# TA_2021_V_2.net
KiCad netlist of a schematic drawn in EAGLE
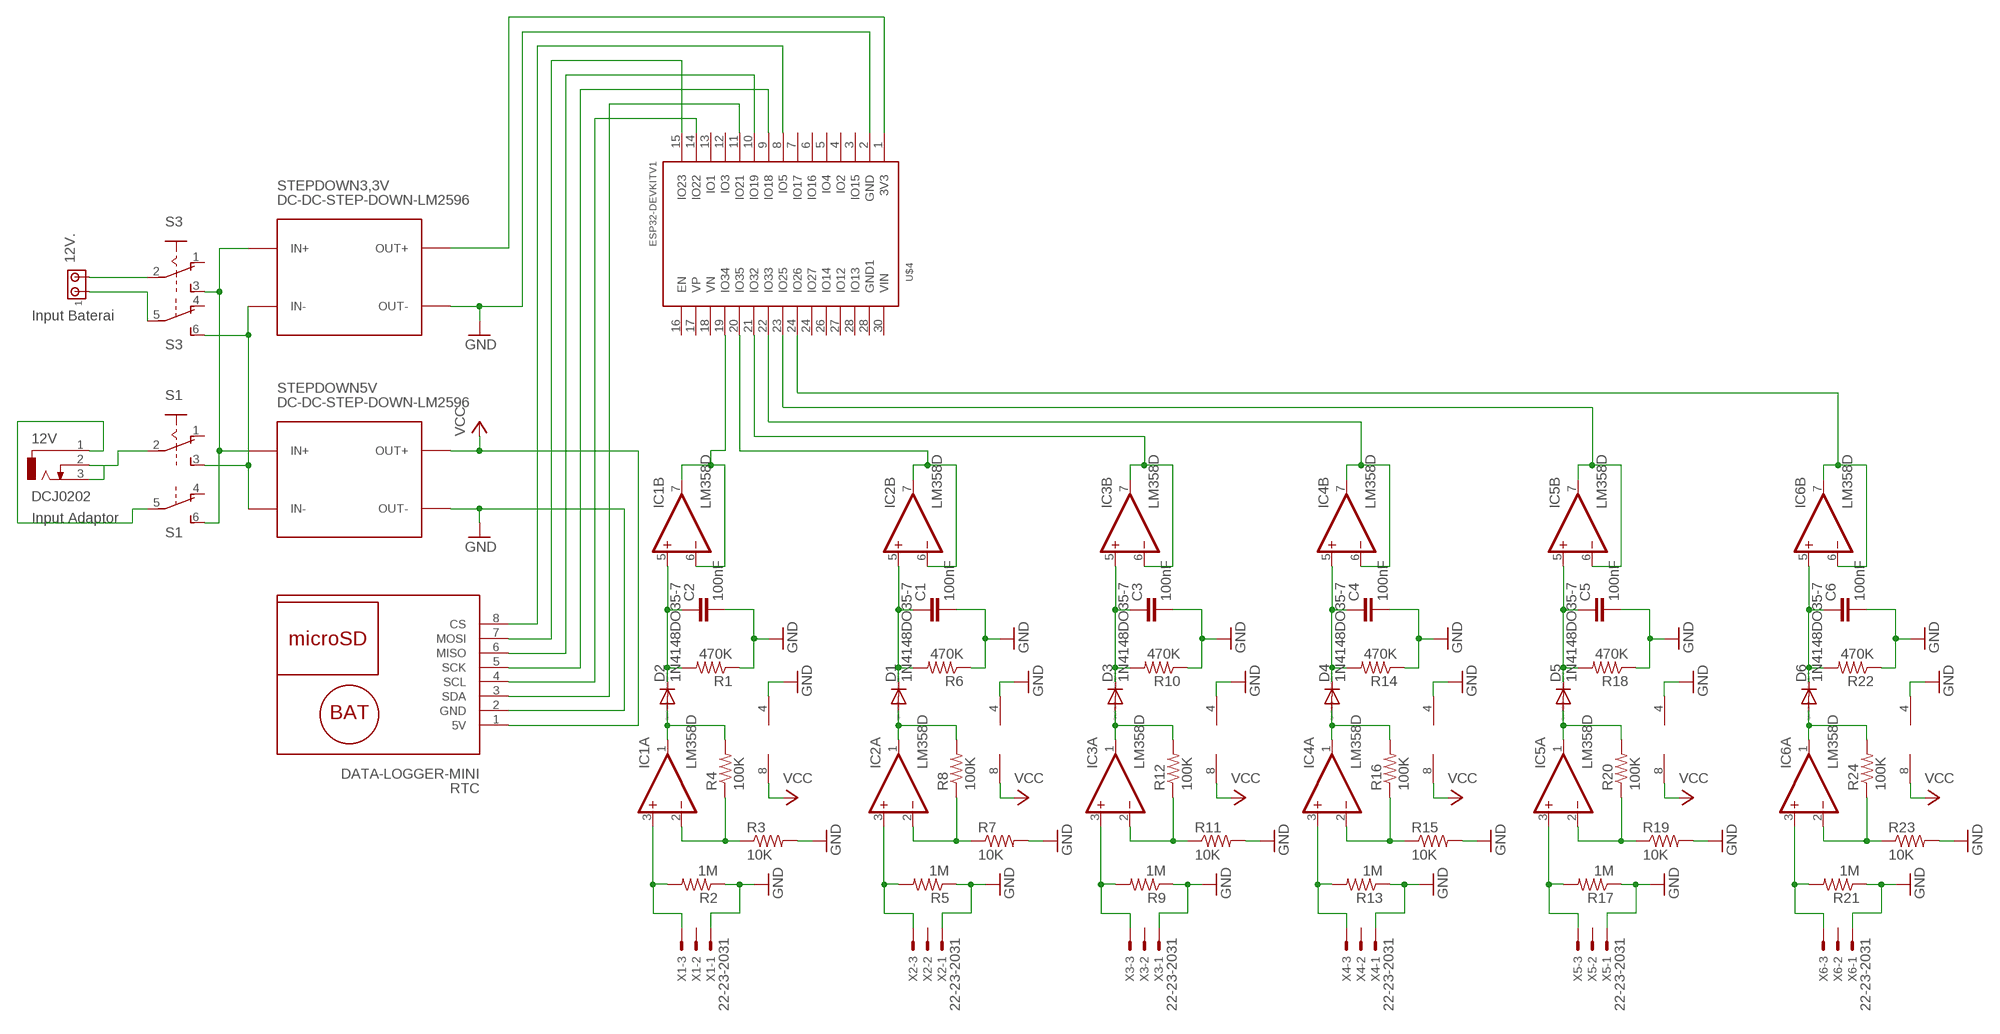
[diagram p0: schematic, sheet 1]

(export (version "E")
  (design (tool "Eeschema 10.0.6"))
  (components
    (comp (ref "12V")
      (value "DCJ0202")
      (footprint "eagle-import:DCJ0202")
      (libsource (lib "eagle-import") (part "DCJ0202"))
    )
    (comp (ref "12V.")
      (value "MTA02-156")
      (footprint "eagle-import:1X2MTA")
      (libsource (lib "eagle-import") (part "MTA02-156"))
    )
    (comp (ref "C1")
      (value "100nF")
      (footprint "eagle-import:C075-032X103")
      (libsource (lib "eagle-import") (part "C-EU075-032X103"))
    )
    (comp (ref "C2")
      (value "100nF")
      (footprint "eagle-import:C075-032X103")
      (libsource (lib "eagle-import") (part "C-EU075-032X103"))
    )
    (comp (ref "C3")
      (value "100nF")
      (footprint "eagle-import:C075-032X103")
      (libsource (lib "eagle-import") (part "C-EU075-032X103"))
    )
    (comp (ref "C4")
      (value "100nF")
      (footprint "eagle-import:C075-032X103")
      (libsource (lib "eagle-import") (part "C-EU075-032X103"))
    )
    (comp (ref "C5")
      (value "100nF")
      (footprint "eagle-import:C075-032X103")
      (libsource (lib "eagle-import") (part "C-EU075-032X103"))
    )
    (comp (ref "C6")
      (value "100nF")
      (footprint "eagle-import:C075-032X103")
      (libsource (lib "eagle-import") (part "C-EU075-032X103"))
    )
    (comp (ref "D1")
      (value "1N4148DO35-7")
      (footprint "eagle-import:DO35-7")
      (libsource (lib "eagle-import") (part "1N4148DO35-7"))
    )
    (comp (ref "D2")
      (value "1N4148DO35-7")
      (footprint "eagle-import:DO35-7")
      (libsource (lib "eagle-import") (part "1N4148DO35-7"))
    )
    (comp (ref "D3")
      (value "1N4148DO35-7")
      (footprint "eagle-import:DO35-7")
      (libsource (lib "eagle-import") (part "1N4148DO35-7"))
    )
    (comp (ref "D4")
      (value "1N4148DO35-7")
      (footprint "eagle-import:DO35-7")
      (libsource (lib "eagle-import") (part "1N4148DO35-7"))
    )
    (comp (ref "D5")
      (value "1N4148DO35-7")
      (footprint "eagle-import:DO35-7")
      (libsource (lib "eagle-import") (part "1N4148DO35-7"))
    )
    (comp (ref "D6")
      (value "1N4148DO35-7")
      (footprint "eagle-import:DO35-7")
      (libsource (lib "eagle-import") (part "1N4148DO35-7"))
    )
    (comp (ref "IC1")
      (value "LM358D")
      (footprint "eagle-import:SO08")
      (libsource (lib "eagle-import") (part "LM358D"))
    )
    (comp (ref "IC2")
      (value "LM358D")
      (footprint "eagle-import:SO08")
      (libsource (lib "eagle-import") (part "LM358D"))
    )
    (comp (ref "IC3")
      (value "LM358D")
      (footprint "eagle-import:SO08")
      (libsource (lib "eagle-import") (part "LM358D"))
    )
    (comp (ref "IC4")
      (value "LM358D")
      (footprint "eagle-import:SO08")
      (libsource (lib "eagle-import") (part "LM358D"))
    )
    (comp (ref "IC5")
      (value "LM358D")
      (footprint "eagle-import:SO08")
      (libsource (lib "eagle-import") (part "LM358D"))
    )
    (comp (ref "IC6")
      (value "LM358D")
      (footprint "eagle-import:SO08")
      (libsource (lib "eagle-import") (part "LM358D"))
    )
    (comp (ref "R1")
      (value "470K")
      (footprint "eagle-import:0207_10")
      (libsource (lib "eagle-import") (part "R-US_0207/10"))
    )
    (comp (ref "R2")
      (value "1M")
      (footprint "eagle-import:0207_10")
      (libsource (lib "eagle-import") (part "R-US_0207/10"))
    )
    (comp (ref "R3")
      (value "10K")
      (footprint "eagle-import:0207_10")
      (libsource (lib "eagle-import") (part "R-US_0207/10"))
    )
    (comp (ref "R4")
      (value "100K")
      (footprint "eagle-import:0207_10")
      (libsource (lib "eagle-import") (part "R-US_0207/10"))
    )
    (comp (ref "R5")
      (value "1M")
      (footprint "eagle-import:0207_10")
      (libsource (lib "eagle-import") (part "R-US_0207/10"))
    )
    (comp (ref "R6")
      (value "470K")
      (footprint "eagle-import:0207_10")
      (libsource (lib "eagle-import") (part "R-US_0207/10"))
    )
    (comp (ref "R7")
      (value "10K")
      (footprint "eagle-import:0207_10")
      (libsource (lib "eagle-import") (part "R-US_0207/10"))
    )
    (comp (ref "R8")
      (value "100K")
      (footprint "eagle-import:0207_10")
      (libsource (lib "eagle-import") (part "R-US_0207/10"))
    )
    (comp (ref "R9")
      (value "1M")
      (footprint "eagle-import:0207_10")
      (libsource (lib "eagle-import") (part "R-US_0207/10"))
    )
    (comp (ref "R10")
      (value "470K")
      (footprint "eagle-import:0207_10")
      (libsource (lib "eagle-import") (part "R-US_0207/10"))
    )
    (comp (ref "R11")
      (value "10K")
      (footprint "eagle-import:0207_10")
      (libsource (lib "eagle-import") (part "R-US_0207/10"))
    )
    (comp (ref "R12")
      (value "100K")
      (footprint "eagle-import:0207_10")
      (libsource (lib "eagle-import") (part "R-US_0207/10"))
    )
    (comp (ref "R13")
      (value "1M")
      (footprint "eagle-import:0207_10")
      (libsource (lib "eagle-import") (part "R-US_0207/10"))
    )
    (comp (ref "R14")
      (value "470K")
      (footprint "eagle-import:0207_10")
      (libsource (lib "eagle-import") (part "R-US_0207/10"))
    )
    (comp (ref "R15")
      (value "10K")
      (footprint "eagle-import:0207_10")
      (libsource (lib "eagle-import") (part "R-US_0207/10"))
    )
    (comp (ref "R16")
      (value "100K")
      (footprint "eagle-import:0207_10")
      (libsource (lib "eagle-import") (part "R-US_0207/10"))
    )
    (comp (ref "R17")
      (value "1M")
      (footprint "eagle-import:0207_10")
      (libsource (lib "eagle-import") (part "R-US_0207/10"))
    )
    (comp (ref "R18")
      (value "470K")
      (footprint "eagle-import:0207_10")
      (libsource (lib "eagle-import") (part "R-US_0207/10"))
    )
    (comp (ref "R19")
      (value "10K")
      (footprint "eagle-import:0207_10")
      (libsource (lib "eagle-import") (part "R-US_0207/10"))
    )
    (comp (ref "R20")
      (value "100K")
      (footprint "eagle-import:0207_10")
      (libsource (lib "eagle-import") (part "R-US_0207/10"))
    )
    (comp (ref "R21")
      (value "1M")
      (footprint "eagle-import:0207_10")
      (libsource (lib "eagle-import") (part "R-US_0207/10"))
    )
    (comp (ref "R22")
      (value "470K")
      (footprint "eagle-import:0207_10")
      (libsource (lib "eagle-import") (part "R-US_0207/10"))
    )
    (comp (ref "R23")
      (value "10K")
      (footprint "eagle-import:0207_10")
      (libsource (lib "eagle-import") (part "R-US_0207/10"))
    )
    (comp (ref "R24")
      (value "100K")
      (footprint "eagle-import:0207_10")
      (libsource (lib "eagle-import") (part "R-US_0207/10"))
    )
    (comp (ref "RTC")
      (value "DATA-LOGGER-MINI")
      (footprint "eagle-import:DATA-LOGGER-MINI")
      (libsource (lib "eagle-import") (part "DATA-LOGGER-MINI"))
    )
    (comp (ref "S1")
      (value "A68-A31")
      (footprint "eagle-import:A68-A31")
      (libsource (lib "eagle-import") (part "A68-A31"))
    )
    (comp (ref "S3")
      (value "A68-A31")
      (footprint "eagle-import:A68-A31")
      (libsource (lib "eagle-import") (part "A68-A31"))
    )
    (comp (ref "STEPDOWN3,3V")
      (value "DC-DC-STEP-DOWN-LM2596")
      (footprint "eagle-import:DC-DC-STEP-DOWN-LM2596")
      (libsource (lib "eagle-import") (part "DC-DC-STEP-DOWN-LM2596"))
    )
    (comp (ref "STEPDOWN5V")
      (value "DC-DC-STEP-DOWN-LM2596")
      (footprint "eagle-import:DC-DC-STEP-DOWN-LM2596")
      (libsource (lib "eagle-import") (part "DC-DC-STEP-DOWN-LM2596"))
    )
    (comp (ref "U$4")
      (value "ESP32DEVKITV1")
      (footprint "eagle-import:ESP32-DEVKITV1")
      (libsource (lib "eagle-import") (part "ESP32DEVKITV1"))
    )
    (comp (ref "X1")
      (value "22-23-2031")
      (footprint "eagle-import:22-23-2031")
      (fields (field (name "MF") "MOLEX"))
      (libsource (lib "eagle-import") (part "22-23-2031"))
    )
    (comp (ref "X2")
      (value "22-23-2031")
      (footprint "eagle-import:22-23-2031")
      (fields (field (name "MF") "MOLEX"))
      (libsource (lib "eagle-import") (part "22-23-2031"))
    )
    (comp (ref "X3")
      (value "22-23-2031")
      (footprint "eagle-import:22-23-2031")
      (fields (field (name "MF") "MOLEX"))
      (libsource (lib "eagle-import") (part "22-23-2031"))
    )
    (comp (ref "X4")
      (value "22-23-2031")
      (footprint "eagle-import:22-23-2031")
      (fields (field (name "MF") "MOLEX"))
      (libsource (lib "eagle-import") (part "22-23-2031"))
    )
    (comp (ref "X5")
      (value "22-23-2031")
      (footprint "eagle-import:22-23-2031")
      (fields (field (name "MF") "MOLEX"))
      (libsource (lib "eagle-import") (part "22-23-2031"))
    )
    (comp (ref "X6")
      (value "22-23-2031")
      (footprint "eagle-import:22-23-2031")
      (fields (field (name "MF") "MOLEX"))
      (libsource (lib "eagle-import") (part "22-23-2031"))
    )
  )
  (nets
    (net (code "1") (name "GND") (class "Default")
      (node (ref "C1") (pin "2") (pinfunction "2_2") (pintype "passive"))
      (node (ref "C2") (pin "2") (pinfunction "2_2") (pintype "passive"))
      (node (ref "C3") (pin "2") (pinfunction "2_2") (pintype "passive"))
      (node (ref "C4") (pin "2") (pinfunction "2_2") (pintype "passive"))
      (node (ref "C5") (pin "2") (pinfunction "2_2") (pintype "passive"))
      (node (ref "C6") (pin "2") (pinfunction "2_2") (pintype "passive"))
      (node (ref "IC1") (pin "4") (pinfunction "V-_4") (pintype "power_in"))
      (node (ref "IC2") (pin "4") (pinfunction "V-_4") (pintype "power_in"))
      (node (ref "IC3") (pin "4") (pinfunction "V-_4") (pintype "power_in"))
      (node (ref "IC4") (pin "4") (pinfunction "V-_4") (pintype "power_in"))
      (node (ref "IC5") (pin "4") (pinfunction "V-_4") (pintype "power_in"))
      (node (ref "IC6") (pin "4") (pinfunction "V-_4") (pintype "power_in"))
      (node (ref "R1") (pin "1") (pinfunction "1_1") (pintype "passive"))
      (node (ref "R10") (pin "1") (pinfunction "1_1") (pintype "passive"))
      (node (ref "R11") (pin "2") (pinfunction "2_2") (pintype "passive"))
      (node (ref "R13") (pin "1") (pinfunction "1_1") (pintype "passive"))
      (node (ref "R14") (pin "1") (pinfunction "1_1") (pintype "passive"))
      (node (ref "R15") (pin "2") (pinfunction "2_2") (pintype "passive"))
      (node (ref "R17") (pin "1") (pinfunction "1_1") (pintype "passive"))
      (node (ref "R18") (pin "1") (pinfunction "1_1") (pintype "passive"))
      (node (ref "R19") (pin "2") (pinfunction "2_2") (pintype "passive"))
      (node (ref "R2") (pin "1") (pinfunction "1_1") (pintype "passive"))
      (node (ref "R21") (pin "1") (pinfunction "1_1") (pintype "passive"))
      (node (ref "R22") (pin "1") (pinfunction "1_1") (pintype "passive"))
      (node (ref "R23") (pin "2") (pinfunction "2_2") (pintype "passive"))
      (node (ref "R3") (pin "2") (pinfunction "2_2") (pintype "passive"))
      (node (ref "R5") (pin "1") (pinfunction "1_1") (pintype "passive"))
      (node (ref "R6") (pin "1") (pinfunction "1_1") (pintype "passive"))
      (node (ref "R7") (pin "2") (pinfunction "2_2") (pintype "passive"))
      (node (ref "R9") (pin "1") (pinfunction "1_1") (pintype "passive"))
      (node (ref "RTC") (pin "2") (pinfunction "GND_2") (pintype "power_in"))
      (node (ref "STEPDOWN3,3V") (pin "OUT-") (pinfunction "OUT-_OUT-") (pintype "bidirectional"))
      (node (ref "STEPDOWN5V") (pin "OUT-") (pinfunction "OUT-_OUT-") (pintype "bidirectional"))
      (node (ref "U$4") (pin "2") (pinfunction "GND_2") (pintype "bidirectional"))
      (node (ref "X1") (pin "1") (pinfunction "S_1") (pintype "passive"))
      (node (ref "X2") (pin "1") (pinfunction "S_1") (pintype "passive"))
      (node (ref "X3") (pin "1") (pinfunction "S_1") (pintype "passive"))
      (node (ref "X4") (pin "1") (pinfunction "S_1") (pintype "passive"))
      (node (ref "X5") (pin "1") (pinfunction "S_1") (pintype "passive"))
      (node (ref "X6") (pin "1") (pinfunction "S_1") (pintype "passive"))
    )
    (net (code "2") (name "Net-(IC1A-+IN)") (class "Default")
      (node (ref "IC1") (pin "3") (pinfunction "+IN_3") (pintype "input"))
      (node (ref "R2") (pin "2") (pinfunction "2_2") (pintype "passive"))
      (node (ref "X1") (pin "3") (pinfunction "S_3") (pintype "passive"))
    )
    (net (code "3") (name "Net-(IC1A--IN)") (class "Default")
      (node (ref "IC1") (pin "2") (pinfunction "-IN_2") (pintype "input"))
      (node (ref "R3") (pin "1") (pinfunction "1_1") (pintype "passive"))
      (node (ref "R4") (pin "1") (pinfunction "1_1") (pintype "passive"))
    )
    (net (code "4") (name "Net-(IC1A-OUT)") (class "Default")
      (node (ref "D2") (pin "A") (pinfunction "A_A") (pintype "passive"))
      (node (ref "IC1") (pin "1") (pinfunction "OUT_1") (pintype "output"))
      (node (ref "R4") (pin "2") (pinfunction "2_2") (pintype "passive"))
    )
    (net (code "5") (name "Net-(IC1B-+IN)") (class "Default")
      (node (ref "C2") (pin "1") (pinfunction "1_1") (pintype "passive"))
      (node (ref "D2") (pin "C") (pinfunction "C_C") (pintype "passive"))
      (node (ref "IC1") (pin "5") (pinfunction "+IN_5") (pintype "input"))
      (node (ref "R1") (pin "2") (pinfunction "2_2") (pintype "passive"))
    )
    (net (code "6") (name "Net-(IC1B--IN)") (class "Default")
      (node (ref "IC1") (pin "6") (pinfunction "-IN_6") (pintype "input"))
      (node (ref "IC1") (pin "7") (pinfunction "OUT_7") (pintype "output"))
      (node (ref "U$4") (pin "19") (pinfunction "IO34_19") (pintype "bidirectional"))
    )
    (net (code "7") (name "Net-(IC2A-+IN)") (class "Default")
      (node (ref "IC2") (pin "3") (pinfunction "+IN_3") (pintype "input"))
      (node (ref "R5") (pin "2") (pinfunction "2_2") (pintype "passive"))
      (node (ref "X2") (pin "3") (pinfunction "S_3") (pintype "passive"))
    )
    (net (code "8") (name "Net-(IC2A--IN)") (class "Default")
      (node (ref "IC2") (pin "2") (pinfunction "-IN_2") (pintype "input"))
      (node (ref "R7") (pin "1") (pinfunction "1_1") (pintype "passive"))
      (node (ref "R8") (pin "1") (pinfunction "1_1") (pintype "passive"))
    )
    (net (code "9") (name "Net-(IC2A-OUT)") (class "Default")
      (node (ref "D1") (pin "A") (pinfunction "A_A") (pintype "passive"))
      (node (ref "IC2") (pin "1") (pinfunction "OUT_1") (pintype "output"))
      (node (ref "R8") (pin "2") (pinfunction "2_2") (pintype "passive"))
    )
    (net (code "10") (name "Net-(IC2B-+IN)") (class "Default")
      (node (ref "C1") (pin "1") (pinfunction "1_1") (pintype "passive"))
      (node (ref "D1") (pin "C") (pinfunction "C_C") (pintype "passive"))
      (node (ref "IC2") (pin "5") (pinfunction "+IN_5") (pintype "input"))
      (node (ref "R6") (pin "2") (pinfunction "2_2") (pintype "passive"))
    )
    (net (code "11") (name "Net-(IC2B--IN)") (class "Default")
      (node (ref "IC2") (pin "6") (pinfunction "-IN_6") (pintype "input"))
      (node (ref "IC2") (pin "7") (pinfunction "OUT_7") (pintype "output"))
      (node (ref "U$4") (pin "20") (pinfunction "IO35_20") (pintype "bidirectional"))
    )
    (net (code "12") (name "Net-(IC3A-+IN)") (class "Default")
      (node (ref "IC3") (pin "3") (pinfunction "+IN_3") (pintype "input"))
      (node (ref "R9") (pin "2") (pinfunction "2_2") (pintype "passive"))
      (node (ref "X3") (pin "3") (pinfunction "S_3") (pintype "passive"))
    )
    (net (code "13") (name "Net-(IC3A--IN)") (class "Default")
      (node (ref "IC3") (pin "2") (pinfunction "-IN_2") (pintype "input"))
      (node (ref "R11") (pin "1") (pinfunction "1_1") (pintype "passive"))
      (node (ref "R12") (pin "1") (pinfunction "1_1") (pintype "passive"))
    )
    (net (code "14") (name "Net-(IC3A-OUT)") (class "Default")
      (node (ref "D3") (pin "A") (pinfunction "A_A") (pintype "passive"))
      (node (ref "IC3") (pin "1") (pinfunction "OUT_1") (pintype "output"))
      (node (ref "R12") (pin "2") (pinfunction "2_2") (pintype "passive"))
    )
    (net (code "15") (name "Net-(IC3B-+IN)") (class "Default")
      (node (ref "C3") (pin "1") (pinfunction "1_1") (pintype "passive"))
      (node (ref "D3") (pin "C") (pinfunction "C_C") (pintype "passive"))
      (node (ref "IC3") (pin "5") (pinfunction "+IN_5") (pintype "input"))
      (node (ref "R10") (pin "2") (pinfunction "2_2") (pintype "passive"))
    )
    (net (code "16") (name "Net-(IC3B--IN)") (class "Default")
      (node (ref "IC3") (pin "6") (pinfunction "-IN_6") (pintype "input"))
      (node (ref "IC3") (pin "7") (pinfunction "OUT_7") (pintype "output"))
      (node (ref "U$4") (pin "21") (pinfunction "IO32_21") (pintype "bidirectional"))
    )
    (net (code "17") (name "Net-(IC4A-+IN)") (class "Default")
      (node (ref "IC4") (pin "3") (pinfunction "+IN_3") (pintype "input"))
      (node (ref "R13") (pin "2") (pinfunction "2_2") (pintype "passive"))
      (node (ref "X4") (pin "3") (pinfunction "S_3") (pintype "passive"))
    )
    (net (code "18") (name "Net-(IC4A--IN)") (class "Default")
      (node (ref "IC4") (pin "2") (pinfunction "-IN_2") (pintype "input"))
      (node (ref "R15") (pin "1") (pinfunction "1_1") (pintype "passive"))
      (node (ref "R16") (pin "1") (pinfunction "1_1") (pintype "passive"))
    )
    (net (code "19") (name "Net-(IC4A-OUT)") (class "Default")
      (node (ref "D4") (pin "A") (pinfunction "A_A") (pintype "passive"))
      (node (ref "IC4") (pin "1") (pinfunction "OUT_1") (pintype "output"))
      (node (ref "R16") (pin "2") (pinfunction "2_2") (pintype "passive"))
    )
    (net (code "20") (name "Net-(IC4B-+IN)") (class "Default")
      (node (ref "C4") (pin "1") (pinfunction "1_1") (pintype "passive"))
      (node (ref "D4") (pin "C") (pinfunction "C_C") (pintype "passive"))
      (node (ref "IC4") (pin "5") (pinfunction "+IN_5") (pintype "input"))
      (node (ref "R14") (pin "2") (pinfunction "2_2") (pintype "passive"))
    )
    (net (code "21") (name "Net-(IC4B--IN)") (class "Default")
      (node (ref "IC4") (pin "6") (pinfunction "-IN_6") (pintype "input"))
      (node (ref "IC4") (pin "7") (pinfunction "OUT_7") (pintype "output"))
      (node (ref "U$4") (pin "22") (pinfunction "IO33_22") (pintype "bidirectional"))
    )
    (net (code "22") (name "Net-(IC5A-+IN)") (class "Default")
      (node (ref "IC5") (pin "3") (pinfunction "+IN_3") (pintype "input"))
      (node (ref "R17") (pin "2") (pinfunction "2_2") (pintype "passive"))
      (node (ref "X5") (pin "3") (pinfunction "S_3") (pintype "passive"))
    )
    (net (code "23") (name "Net-(IC5A--IN)") (class "Default")
      (node (ref "IC5") (pin "2") (pinfunction "-IN_2") (pintype "input"))
      (node (ref "R19") (pin "1") (pinfunction "1_1") (pintype "passive"))
      (node (ref "R20") (pin "1") (pinfunction "1_1") (pintype "passive"))
    )
    (net (code "24") (name "Net-(IC5A-OUT)") (class "Default")
      (node (ref "D5") (pin "A") (pinfunction "A_A") (pintype "passive"))
      (node (ref "IC5") (pin "1") (pinfunction "OUT_1") (pintype "output"))
      (node (ref "R20") (pin "2") (pinfunction "2_2") (pintype "passive"))
    )
    (net (code "25") (name "Net-(IC5B-+IN)") (class "Default")
      (node (ref "C5") (pin "1") (pinfunction "1_1") (pintype "passive"))
      (node (ref "D5") (pin "C") (pinfunction "C_C") (pintype "passive"))
      (node (ref "IC5") (pin "5") (pinfunction "+IN_5") (pintype "input"))
      (node (ref "R18") (pin "2") (pinfunction "2_2") (pintype "passive"))
    )
    (net (code "26") (name "Net-(IC5B--IN)") (class "Default")
      (node (ref "IC5") (pin "6") (pinfunction "-IN_6") (pintype "input"))
      (node (ref "IC5") (pin "7") (pinfunction "OUT_7") (pintype "output"))
      (node (ref "U$4") (pin "23") (pinfunction "IO25_23") (pintype "bidirectional"))
    )
    (net (code "27") (name "Net-(IC6A-+IN)") (class "Default")
      (node (ref "IC6") (pin "3") (pinfunction "+IN_3") (pintype "input"))
      (node (ref "R21") (pin "2") (pinfunction "2_2") (pintype "passive"))
      (node (ref "X6") (pin "3") (pinfunction "S_3") (pintype "passive"))
    )
    (net (code "28") (name "Net-(IC6A--IN)") (class "Default")
      (node (ref "IC6") (pin "2") (pinfunction "-IN_2") (pintype "input"))
      (node (ref "R23") (pin "1") (pinfunction "1_1") (pintype "passive"))
      (node (ref "R24") (pin "1") (pinfunction "1_1") (pintype "passive"))
    )
    (net (code "29") (name "Net-(IC6A-OUT)") (class "Default")
      (node (ref "D6") (pin "A") (pinfunction "A_A") (pintype "passive"))
      (node (ref "IC6") (pin "1") (pinfunction "OUT_1") (pintype "output"))
      (node (ref "R24") (pin "2") (pinfunction "2_2") (pintype "passive"))
    )
    (net (code "30") (name "Net-(IC6B-+IN)") (class "Default")
      (node (ref "C6") (pin "1") (pinfunction "1_1") (pintype "passive"))
      (node (ref "D6") (pin "C") (pinfunction "C_C") (pintype "passive"))
      (node (ref "IC6") (pin "5") (pinfunction "+IN_5") (pintype "input"))
      (node (ref "R22") (pin "2") (pinfunction "2_2") (pintype "passive"))
    )
    (net (code "31") (name "Net-(IC6B--IN)") (class "Default")
      (node (ref "IC6") (pin "6") (pinfunction "-IN_6") (pintype "input"))
      (node (ref "IC6") (pin "7") (pinfunction "OUT_7") (pintype "output"))
      (node (ref "U$4") (pin "24") (pinfunction "IO26_24") (pintype "bidirectional"))
    )
    (net (code "32") (name "Net-(RTC-CS)") (class "Default")
      (node (ref "RTC") (pin "8") (pinfunction "CS_8") (pintype "power_in"))
      (node (ref "U$4") (pin "8") (pinfunction "IO5_8") (pintype "bidirectional"))
    )
    (net (code "33") (name "Net-(RTC-MISO)") (class "Default")
      (node (ref "RTC") (pin "6") (pinfunction "MISO_6") (pintype "bidirectional"))
      (node (ref "U$4") (pin "10") (pinfunction "IO19_10") (pintype "bidirectional"))
    )
    (net (code "34") (name "Net-(RTC-MOSI)") (class "Default")
      (node (ref "RTC") (pin "7") (pinfunction "MOSI_7") (pintype "bidirectional"))
      (node (ref "U$4") (pin "15") (pinfunction "IO23_15") (pintype "bidirectional"))
    )
    (net (code "35") (name "Net-(RTC-SCK)") (class "Default")
      (node (ref "RTC") (pin "5") (pinfunction "SCK_5") (pintype "bidirectional"))
      (node (ref "U$4") (pin "9") (pinfunction "IO18_9") (pintype "bidirectional"))
    )
    (net (code "36") (name "Net-(RTC-SCL)") (class "Default")
      (node (ref "RTC") (pin "4") (pinfunction "SCL_4") (pintype "bidirectional"))
      (node (ref "U$4") (pin "14") (pinfunction "IO22_14") (pintype "bidirectional"))
    )
    (net (code "37") (name "Net-(RTC-SDA)") (class "Default")
      (node (ref "RTC") (pin "3") (pinfunction "SDA_3") (pintype "bidirectional"))
      (node (ref "U$4") (pin "11") (pinfunction "IO21_11") (pintype "bidirectional"))
    )
    (net (code "38") (name "Net-(S1A-P)") (class "Default")
      (node (ref "12V") (pin "2") (pinfunction "2_2") (pintype "passive"))
      (node (ref "12V") (pin "3") (pinfunction "3_3") (pintype "passive"))
      (node (ref "S1") (pin "2") (pinfunction "P_2") (pintype "passive"))
    )
    (net (code "39") (name "Net-(S1A-S)") (class "Default")
      (node (ref "S1") (pin "3") (pinfunction "S_3") (pintype "passive"))
      (node (ref "S3") (pin "6") (pinfunction "S_6") (pintype "passive"))
      (node (ref "STEPDOWN3,3V") (pin "IN-") (pinfunction "IN-_IN-") (pintype "bidirectional"))
      (node (ref "STEPDOWN5V") (pin "IN-") (pinfunction "IN-_IN-") (pintype "bidirectional"))
    )
    (net (code "40") (name "Net-(S1B-P)") (class "Default")
      (node (ref "12V") (pin "1") (pinfunction "1_1") (pintype "passive"))
      (node (ref "S1") (pin "5") (pinfunction "P_5") (pintype "passive"))
    )
    (net (code "41") (name "Net-(S1B-S)") (class "Default")
      (node (ref "S1") (pin "6") (pinfunction "S_6") (pintype "passive"))
      (node (ref "S3") (pin "3") (pinfunction "S_3") (pintype "passive"))
      (node (ref "STEPDOWN3,3V") (pin "IN+") (pinfunction "IN+_IN+") (pintype "bidirectional"))
      (node (ref "STEPDOWN5V") (pin "IN+") (pinfunction "IN+_IN+") (pintype "bidirectional"))
    )
    (net (code "42") (name "Net-(S3A-P)") (class "Default")
      (node (ref "12V.") (pin "2") (pinfunction "2_2") (pintype "passive"))
      (node (ref "S3") (pin "2") (pinfunction "P_2") (pintype "passive"))
    )
    (net (code "43") (name "Net-(S3B-P)") (class "Default")
      (node (ref "12V.") (pin "1") (pinfunction "1_1") (pintype "passive"))
      (node (ref "S3") (pin "5") (pinfunction "P_5") (pintype "passive"))
    )
    (net (code "44") (name "Net-(U$4-3V3)") (class "Default")
      (node (ref "STEPDOWN3,3V") (pin "OUT+") (pinfunction "OUT+_OUT+") (pintype "bidirectional"))
      (node (ref "U$4") (pin "1") (pinfunction "3V3_1") (pintype "bidirectional"))
    )
    (net (code "45") (name "VCC") (class "Default")
      (node (ref "IC1") (pin "8") (pinfunction "V+_8") (pintype "power_in"))
      (node (ref "IC2") (pin "8") (pinfunction "V+_8") (pintype "power_in"))
      (node (ref "IC3") (pin "8") (pinfunction "V+_8") (pintype "power_in"))
      (node (ref "IC4") (pin "8") (pinfunction "V+_8") (pintype "power_in"))
      (node (ref "IC5") (pin "8") (pinfunction "V+_8") (pintype "power_in"))
      (node (ref "IC6") (pin "8") (pinfunction "V+_8") (pintype "power_in"))
      (node (ref "RTC") (pin "1") (pinfunction "5V_1") (pintype "power_in"))
      (node (ref "STEPDOWN5V") (pin "OUT+") (pinfunction "OUT+_OUT+") (pintype "bidirectional"))
    )
    (net (code "46") (name "unconnected-(S1A-O-Pad1)") (class "Default")
      (node (ref "S1") (pin "1") (pinfunction "O_1") (pintype "passive"))
    )
    (net (code "47") (name "unconnected-(S1B-O-Pad4)") (class "Default")
      (node (ref "S1") (pin "4") (pinfunction "O_4") (pintype "passive"))
    )
    (net (code "48") (name "unconnected-(S3A-O-Pad1)") (class "Default")
      (node (ref "S3") (pin "1") (pinfunction "O_1") (pintype "passive"))
    )
    (net (code "49") (name "unconnected-(S3B-O-Pad4)") (class "Default")
      (node (ref "S3") (pin "4") (pinfunction "O_4") (pintype "passive"))
    )
    (net (code "50") (name "unconnected-(U$4-EN-Pad16)") (class "Default")
      (node (ref "U$4") (pin "16") (pinfunction "EN_16") (pintype "bidirectional"))
    )
    (net (code "51") (name "unconnected-(U$4-GND1-Pad28)") (class "Default")
      (node (ref "U$4") (pin "28") (pinfunction "GND1_28") (pintype "bidirectional"))
    )
    (net (code "52") (name "unconnected-(U$4-IO1-Pad13)") (class "Default")
      (node (ref "U$4") (pin "13") (pinfunction "IO1_13") (pintype "bidirectional"))
    )
    (net (code "53") (name "unconnected-(U$4-IO2-Pad4)") (class "Default")
      (node (ref "U$4") (pin "4") (pinfunction "IO2_4") (pintype "bidirectional"))
    )
    (net (code "54") (name "unconnected-(U$4-IO3-Pad12)") (class "Default")
      (node (ref "U$4") (pin "12") (pinfunction "IO3_12") (pintype "bidirectional"))
    )
    (net (code "55") (name "unconnected-(U$4-IO4-Pad5)") (class "Default")
      (node (ref "U$4") (pin "5") (pinfunction "IO4_5") (pintype "bidirectional"))
    )
    (net (code "56") (name "unconnected-(U$4-IO12-Pad27)") (class "Default")
      (node (ref "U$4") (pin "27") (pinfunction "IO12_27") (pintype "bidirectional"))
    )
    (net (code "57") (name "unconnected-(U$4-IO13-Pad28)") (class "Default")
      (node (ref "U$4") (pin "28") (pinfunction "IO13_28") (pintype "bidirectional"))
    )
    (net (code "58") (name "unconnected-(U$4-IO14-Pad26)") (class "Default")
      (node (ref "U$4") (pin "26") (pinfunction "IO14_26") (pintype "bidirectional"))
    )
    (net (code "59") (name "unconnected-(U$4-IO15-Pad3)") (class "Default")
      (node (ref "U$4") (pin "3") (pinfunction "IO15_3") (pintype "bidirectional"))
    )
    (net (code "60") (name "unconnected-(U$4-IO16-Pad6)") (class "Default")
      (node (ref "U$4") (pin "6") (pinfunction "IO16_6") (pintype "bidirectional"))
    )
    (net (code "61") (name "unconnected-(U$4-IO17-Pad7)") (class "Default")
      (node (ref "U$4") (pin "7") (pinfunction "IO17_7") (pintype "bidirectional"))
    )
    (net (code "62") (name "unconnected-(U$4-IO27-Pad24)") (class "Default")
      (node (ref "U$4") (pin "24") (pinfunction "IO27_24") (pintype "bidirectional"))
    )
    (net (code "63") (name "unconnected-(U$4-VIN-Pad30)") (class "Default")
      (node (ref "U$4") (pin "30") (pinfunction "VIN_30") (pintype "bidirectional"))
    )
    (net (code "64") (name "unconnected-(U$4-VN-Pad18)") (class "Default")
      (node (ref "U$4") (pin "18") (pinfunction "VN_18") (pintype "bidirectional"))
    )
    (net (code "65") (name "unconnected-(U$4-VP-Pad17)") (class "Default")
      (node (ref "U$4") (pin "17") (pinfunction "VP_17") (pintype "bidirectional"))
    )
    (net (code "66") (name "unconnected-(X1B-S-Pad2)") (class "Default")
      (node (ref "X1") (pin "2") (pinfunction "S_2") (pintype "passive"))
    )
    (net (code "67") (name "unconnected-(X2B-S-Pad2)") (class "Default")
      (node (ref "X2") (pin "2") (pinfunction "S_2") (pintype "passive"))
    )
    (net (code "68") (name "unconnected-(X3B-S-Pad2)") (class "Default")
      (node (ref "X3") (pin "2") (pinfunction "S_2") (pintype "passive"))
    )
    (net (code "69") (name "unconnected-(X4B-S-Pad2)") (class "Default")
      (node (ref "X4") (pin "2") (pinfunction "S_2") (pintype "passive"))
    )
    (net (code "70") (name "unconnected-(X5B-S-Pad2)") (class "Default")
      (node (ref "X5") (pin "2") (pinfunction "S_2") (pintype "passive"))
    )
    (net (code "71") (name "unconnected-(X6B-S-Pad2)") (class "Default")
      (node (ref "X6") (pin "2") (pinfunction "S_2") (pintype "passive"))
    )
  )
)
